# goalLight.net
KiCad netlist of a schematic drawn in Altium Designer
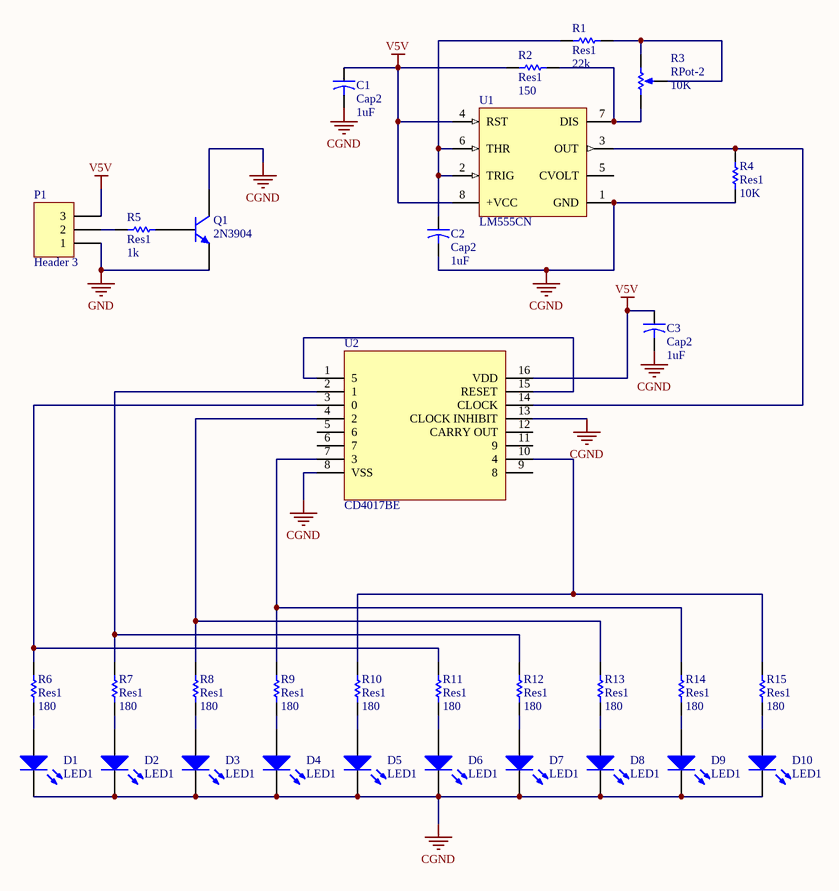
[diagram p0: goalLight.SchDoc]

(export (version "E")
  (design (tool "Eeschema 10.0.6"))
  (components
    (comp (ref "C1")
      (value "Cap2")
      (footprint "CAPR5-4X5")
      (description "Capacitor")
      (fields (field (name "ALTIUM_VALUE") "1uF") (field (name "PUBLISHER") "Altium Limited"))
      (libsource (lib "Miscellaneous Devices") (part "Cap2"))
    )
    (comp (ref "C2")
      (value "Cap2")
      (footprint "CAPR5-4X5")
      (description "Capacitor")
      (fields (field (name "ALTIUM_VALUE") "1uF") (field (name "PUBLISHER") "Altium Limited"))
      (libsource (lib "Miscellaneous Devices") (part "Cap2"))
    )
    (comp (ref "C3")
      (value "Cap2")
      (footprint "CAPR5-4X5")
      (description "Capacitor")
      (fields (field (name "ALTIUM_VALUE") "1uF") (field (name "PUBLISHER") "Altium Limited"))
      (libsource (lib "Miscellaneous Devices") (part "Cap2"))
    )
    (comp (ref "D1")
      (value "LED1")
      (footprint "LED-1")
      (description "Typical RED GaAs LED")
      (fields (field (name "PUBLISHER") "Altium Limited"))
      (libsource (lib "Miscellaneous Devices") (part "LED1"))
    )
    (comp (ref "D2")
      (value "LED1")
      (footprint "LED-1")
      (description "Typical RED GaAs LED")
      (fields (field (name "PUBLISHER") "Altium Limited"))
      (libsource (lib "Miscellaneous Devices") (part "LED1"))
    )
    (comp (ref "D3")
      (value "LED1")
      (footprint "LED-1")
      (description "Typical RED GaAs LED")
      (fields (field (name "PUBLISHER") "Altium Limited"))
      (libsource (lib "Miscellaneous Devices") (part "LED1"))
    )
    (comp (ref "D4")
      (value "LED1")
      (footprint "LED-1")
      (description "Typical RED GaAs LED")
      (fields (field (name "PUBLISHER") "Altium Limited"))
      (libsource (lib "Miscellaneous Devices") (part "LED1"))
    )
    (comp (ref "D5")
      (value "LED1")
      (footprint "LED-1")
      (description "Typical RED GaAs LED")
      (fields (field (name "PUBLISHER") "Altium Limited"))
      (libsource (lib "Miscellaneous Devices") (part "LED1"))
    )
    (comp (ref "D6")
      (value "LED1")
      (footprint "LED-1")
      (description "Typical RED GaAs LED")
      (fields (field (name "PUBLISHER") "Altium Limited"))
      (libsource (lib "Miscellaneous Devices") (part "LED1"))
    )
    (comp (ref "D7")
      (value "LED1")
      (footprint "LED-1")
      (description "Typical RED GaAs LED")
      (fields (field (name "PUBLISHER") "Altium Limited"))
      (libsource (lib "Miscellaneous Devices") (part "LED1"))
    )
    (comp (ref "D8")
      (value "LED1")
      (footprint "LED-1")
      (description "Typical RED GaAs LED")
      (fields (field (name "PUBLISHER") "Altium Limited"))
      (libsource (lib "Miscellaneous Devices") (part "LED1"))
    )
    (comp (ref "D9")
      (value "LED1")
      (footprint "LED-1")
      (description "Typical RED GaAs LED")
      (fields (field (name "PUBLISHER") "Altium Limited"))
      (libsource (lib "Miscellaneous Devices") (part "LED1"))
    )
    (comp (ref "D10")
      (value "LED1")
      (footprint "LED-1")
      (description "Typical RED GaAs LED")
      (fields (field (name "PUBLISHER") "Altium Limited"))
      (libsource (lib "Miscellaneous Devices") (part "LED1"))
    )
    (comp (ref "P1")
      (value "Header 3")
      (footprint "HDR1X3")
      (description "Header, 3-Pin")
      (fields (field (name "PUBLISHER") "Altium Limited"))
      (libsource (lib "Miscellaneous Connectors") (part "Header 3"))
    )
    (comp (ref "Q1")
      (value "2N3904")
      (footprint "TO-92A")
      (description "NPN General Purpose Amplifier")
      (fields (field (name "PUBLISHER") "Altium Limited"))
      (libsource (lib "Miscellaneous Devices") (part "2N3904"))
    )
    (comp (ref "R1")
      (value "Res1")
      (footprint "AXIAL-0.4")
      (description "Resistor")
      (fields (field (name "ALTIUM_VALUE") "22k") (field (name "PUBLISHER") "Altium Limited"))
      (libsource (lib "Miscellaneous Devices") (part "Res1"))
    )
    (comp (ref "R2")
      (value "Res1")
      (footprint "AXIAL-0.4")
      (description "Resistor")
      (fields (field (name "ALTIUM_VALUE") "150") (field (name "PUBLISHER") "Altium Limited"))
      (libsource (lib "Miscellaneous Devices") (part "Res1"))
    )
    (comp (ref "R3")
      (value "RPot-2")
      (footprint "POT3")
      (description "Potentiometer")
      (fields (field (name "ALTIUM_VALUE") "10K") (field (name "PUBLISHER") "Altium Limited"))
      (libsource (lib "components") (part "RPot-2"))
    )
    (comp (ref "R4")
      (value "Res1")
      (footprint "AXIAL-0.4")
      (description "Resistor")
      (fields (field (name "ALTIUM_VALUE") "10K") (field (name "PUBLISHER") "Altium Limited"))
      (libsource (lib "Miscellaneous Devices") (part "Res1"))
    )
    (comp (ref "R5")
      (value "Res1")
      (footprint "AXIAL-0.4")
      (description "Resistor")
      (fields (field (name "ALTIUM_VALUE") "1k") (field (name "PUBLISHER") "Altium Limited"))
      (libsource (lib "Miscellaneous Devices") (part "Res1"))
    )
    (comp (ref "R6")
      (value "Res1")
      (footprint "AXIAL-0.4")
      (description "Resistor")
      (fields (field (name "ALTIUM_VALUE") "180") (field (name "PUBLISHER") "Altium Limited"))
      (libsource (lib "Miscellaneous Devices") (part "Res1"))
    )
    (comp (ref "R7")
      (value "Res1")
      (footprint "AXIAL-0.4")
      (description "Resistor")
      (fields (field (name "ALTIUM_VALUE") "180") (field (name "PUBLISHER") "Altium Limited"))
      (libsource (lib "Miscellaneous Devices") (part "Res1"))
    )
    (comp (ref "R8")
      (value "Res1")
      (footprint "AXIAL-0.4")
      (description "Resistor")
      (fields (field (name "ALTIUM_VALUE") "180") (field (name "PUBLISHER") "Altium Limited"))
      (libsource (lib "Miscellaneous Devices") (part "Res1"))
    )
    (comp (ref "R9")
      (value "Res1")
      (footprint "AXIAL-0.4")
      (description "Resistor")
      (fields (field (name "ALTIUM_VALUE") "180") (field (name "PUBLISHER") "Altium Limited"))
      (libsource (lib "Miscellaneous Devices") (part "Res1"))
    )
    (comp (ref "R10")
      (value "Res1")
      (footprint "AXIAL-0.4")
      (description "Resistor")
      (fields (field (name "ALTIUM_VALUE") "180") (field (name "PUBLISHER") "Altium Limited"))
      (libsource (lib "Miscellaneous Devices") (part "Res1"))
    )
    (comp (ref "R11")
      (value "Res1")
      (footprint "AXIAL-0.4")
      (description "Resistor")
      (fields (field (name "ALTIUM_VALUE") "180") (field (name "PUBLISHER") "Altium Limited"))
      (libsource (lib "Miscellaneous Devices") (part "Res1"))
    )
    (comp (ref "R12")
      (value "Res1")
      (footprint "AXIAL-0.4")
      (description "Resistor")
      (fields (field (name "ALTIUM_VALUE") "180") (field (name "PUBLISHER") "Altium Limited"))
      (libsource (lib "Miscellaneous Devices") (part "Res1"))
    )
    (comp (ref "R13")
      (value "Res1")
      (footprint "AXIAL-0.4")
      (description "Resistor")
      (fields (field (name "ALTIUM_VALUE") "180") (field (name "PUBLISHER") "Altium Limited"))
      (libsource (lib "Miscellaneous Devices") (part "Res1"))
    )
    (comp (ref "R14")
      (value "Res1")
      (footprint "AXIAL-0.4")
      (description "Resistor")
      (fields (field (name "ALTIUM_VALUE") "180") (field (name "PUBLISHER") "Altium Limited"))
      (libsource (lib "Miscellaneous Devices") (part "Res1"))
    )
    (comp (ref "R15")
      (value "Res1")
      (footprint "AXIAL-0.4")
      (description "Resistor")
      (fields (field (name "ALTIUM_VALUE") "180") (field (name "PUBLISHER") "Altium Limited"))
      (libsource (lib "Miscellaneous Devices") (part "Res1"))
    )
    (comp (ref "U1")
      (value "LM555CN")
      (footprint "N08E")
      (description "Timer, 8-pin MDIP")
      (fields
        (field (name "MANUFACTURER") "National Semiconductor")
        (field (name "PUBLISHER") "Altium Limited")
      )
      (libsource (lib "NSC Analog") (part "LM555CN"))
    )
    (comp (ref "U2")
      (value "CD4017BE")
      (footprint "N16")
      (description "Decade Counter")
      (libsource (lib "components") (part "CD4017BE"))
    )
  )
  (nets
    (net (code "1") (name "CGND") (class "Default")
      (node (ref "C1") (pin "2") (pinfunction "2_2") (pintype "passive"))
      (node (ref "C2") (pin "2") (pinfunction "2_2") (pintype "passive"))
      (node (ref "C3") (pin "2") (pinfunction "2_2") (pintype "passive"))
      (node (ref "D1") (pin "2") (pinfunction "K_2") (pintype "passive"))
      (node (ref "D10") (pin "2") (pinfunction "K_2") (pintype "passive"))
      (node (ref "D2") (pin "2") (pinfunction "K_2") (pintype "passive"))
      (node (ref "D3") (pin "2") (pinfunction "K_2") (pintype "passive"))
      (node (ref "D4") (pin "2") (pinfunction "K_2") (pintype "passive"))
      (node (ref "D5") (pin "2") (pinfunction "K_2") (pintype "passive"))
      (node (ref "D6") (pin "2") (pinfunction "K_2") (pintype "passive"))
      (node (ref "D7") (pin "2") (pinfunction "K_2") (pintype "passive"))
      (node (ref "D8") (pin "2") (pinfunction "K_2") (pintype "passive"))
      (node (ref "D9") (pin "2") (pinfunction "K_2") (pintype "passive"))
      (node (ref "Q1") (pin "3") (pinfunction "C_3") (pintype "passive"))
      (node (ref "R4") (pin "1") (pinfunction "1_1") (pintype "passive"))
      (node (ref "U1") (pin "1") (pinfunction "GND_1") (pintype "power_in"))
      (node (ref "U2") (pin "13") (pinfunction "CLOCK_INHIBIT_13") (pintype "passive"))
      (node (ref "U2") (pin "8") (pinfunction "VSS_8") (pintype "passive"))
    )
    (net (code "2") (name "GND") (class "Default")
      (node (ref "P1") (pin "1") (pinfunction "1_1") (pintype "passive"))
      (node (ref "Q1") (pin "1") (pinfunction "E_1") (pintype "passive"))
    )
    (net (code "3") (name "Net-(D1-A)") (class "Default")
      (node (ref "D1") (pin "1") (pinfunction "A_1") (pintype "passive"))
      (node (ref "R6") (pin "1") (pinfunction "1_1") (pintype "passive"))
    )
    (net (code "4") (name "Net-(D2-A)") (class "Default")
      (node (ref "D2") (pin "1") (pinfunction "A_1") (pintype "passive"))
      (node (ref "R7") (pin "1") (pinfunction "1_1") (pintype "passive"))
    )
    (net (code "5") (name "Net-(D3-A)") (class "Default")
      (node (ref "D3") (pin "1") (pinfunction "A_1") (pintype "passive"))
      (node (ref "R8") (pin "1") (pinfunction "1_1") (pintype "passive"))
    )
    (net (code "6") (name "Net-(D4-A)") (class "Default")
      (node (ref "D4") (pin "1") (pinfunction "A_1") (pintype "passive"))
      (node (ref "R9") (pin "1") (pinfunction "1_1") (pintype "passive"))
    )
    (net (code "7") (name "Net-(D5-A)") (class "Default")
      (node (ref "D5") (pin "1") (pinfunction "A_1") (pintype "passive"))
      (node (ref "R10") (pin "1") (pinfunction "1_1") (pintype "passive"))
    )
    (net (code "8") (name "Net-(D6-A)") (class "Default")
      (node (ref "D6") (pin "1") (pinfunction "A_1") (pintype "passive"))
      (node (ref "R11") (pin "1") (pinfunction "1_1") (pintype "passive"))
    )
    (net (code "9") (name "Net-(D7-A)") (class "Default")
      (node (ref "D7") (pin "1") (pinfunction "A_1") (pintype "passive"))
      (node (ref "R12") (pin "1") (pinfunction "1_1") (pintype "passive"))
    )
    (net (code "10") (name "Net-(D8-A)") (class "Default")
      (node (ref "D8") (pin "1") (pinfunction "A_1") (pintype "passive"))
      (node (ref "R13") (pin "1") (pinfunction "1_1") (pintype "passive"))
    )
    (net (code "11") (name "Net-(D9-A)") (class "Default")
      (node (ref "D9") (pin "1") (pinfunction "A_1") (pintype "passive"))
      (node (ref "R14") (pin "1") (pinfunction "1_1") (pintype "passive"))
    )
    (net (code "12") (name "Net-(D10-A)") (class "Default")
      (node (ref "D10") (pin "1") (pinfunction "A_1") (pintype "passive"))
      (node (ref "R15") (pin "1") (pinfunction "1_1") (pintype "passive"))
    )
    (net (code "13") (name "Net-(P1-Pad2)") (class "Default")
      (node (ref "P1") (pin "2") (pinfunction "2_2") (pintype "passive"))
      (node (ref "R5") (pin "2") (pinfunction "2_2") (pintype "passive"))
    )
    (net (code "14") (name "Net-(Q1-B)") (class "Default")
      (node (ref "Q1") (pin "2") (pinfunction "B_2") (pintype "passive"))
      (node (ref "R5") (pin "1") (pinfunction "1_1") (pintype "passive"))
    )
    (net (code "15") (name "Net-(R3-BOT)") (class "Default")
      (node (ref "R1") (pin "1") (pinfunction "1_1") (pintype "passive"))
      (node (ref "R3") (pin "2") (pinfunction "BOT_2") (pintype "passive"))
      (node (ref "R3") (pin "3") (pinfunction "TAP_3") (pintype "passive"))
    )
    (net (code "16") (name "Net-(R3-TOP)") (class "Default")
      (node (ref "R2") (pin "1") (pinfunction "1_1") (pintype "passive"))
      (node (ref "R3") (pin "1") (pinfunction "TOP_1") (pintype "passive"))
      (node (ref "U1") (pin "7") (pinfunction "DIS_7") (pintype "open_collector"))
    )
    (net (code "17") (name "Net-(U1-OUT)") (class "Default")
      (node (ref "R4") (pin "2") (pinfunction "2_2") (pintype "passive"))
      (node (ref "U1") (pin "3") (pinfunction "OUT_3") (pintype "output"))
      (node (ref "U2") (pin "14") (pinfunction "CLOCK_14") (pintype "passive"))
    )
    (net (code "18") (name "Net-(U1-THR)") (class "Default")
      (node (ref "C2") (pin "1") (pinfunction "1_1") (pintype "passive"))
      (node (ref "R1") (pin "2") (pinfunction "2_2") (pintype "passive"))
      (node (ref "U1") (pin "2") (pinfunction "TRIG_2") (pintype "input"))
      (node (ref "U1") (pin "6") (pinfunction "THR_6") (pintype "input"))
    )
    (net (code "19") (name "Net-(U2-0)") (class "Default")
      (node (ref "R11") (pin "2") (pinfunction "2_2") (pintype "passive"))
      (node (ref "R6") (pin "2") (pinfunction "2_2") (pintype "passive"))
      (node (ref "U2") (pin "3") (pinfunction "0_3") (pintype "passive"))
    )
    (net (code "20") (name "Net-(U2-1)") (class "Default")
      (node (ref "R12") (pin "2") (pinfunction "2_2") (pintype "passive"))
      (node (ref "R7") (pin "2") (pinfunction "2_2") (pintype "passive"))
      (node (ref "U2") (pin "2") (pinfunction "1_2") (pintype "passive"))
    )
    (net (code "21") (name "Net-(U2-2)") (class "Default")
      (node (ref "R13") (pin "2") (pinfunction "2_2") (pintype "passive"))
      (node (ref "R8") (pin "2") (pinfunction "2_2") (pintype "passive"))
      (node (ref "U2") (pin "4") (pinfunction "2_4") (pintype "passive"))
    )
    (net (code "22") (name "Net-(U2-3)") (class "Default")
      (node (ref "R14") (pin "2") (pinfunction "2_2") (pintype "passive"))
      (node (ref "R9") (pin "2") (pinfunction "2_2") (pintype "passive"))
      (node (ref "U2") (pin "7") (pinfunction "3_7") (pintype "passive"))
    )
    (net (code "23") (name "Net-(U2-4)") (class "Default")
      (node (ref "R10") (pin "2") (pinfunction "2_2") (pintype "passive"))
      (node (ref "R15") (pin "2") (pinfunction "2_2") (pintype "passive"))
      (node (ref "U2") (pin "10") (pinfunction "4_10") (pintype "passive"))
    )
    (net (code "24") (name "Net-(U2-5)") (class "Default")
      (node (ref "U2") (pin "1") (pinfunction "5_1") (pintype "passive"))
      (node (ref "U2") (pin "15") (pinfunction "RESET_15") (pintype "passive"))
    )
    (net (code "25") (name "V5V") (class "Default")
      (node (ref "C1") (pin "1") (pinfunction "1_1") (pintype "passive"))
      (node (ref "C3") (pin "1") (pinfunction "1_1") (pintype "passive"))
      (node (ref "P1") (pin "3") (pinfunction "3_3") (pintype "passive"))
      (node (ref "R2") (pin "2") (pinfunction "2_2") (pintype "passive"))
      (node (ref "U1") (pin "4") (pinfunction "RST_4") (pintype "input"))
      (node (ref "U1") (pin "8") (pinfunction "+VCC_8") (pintype "power_in"))
      (node (ref "U2") (pin "16") (pinfunction "VDD_16") (pintype "passive"))
    )
    (net (code "26") (name "unconnected-(U1-CVOLT-Pad5)") (class "Default")
      (node (ref "U1") (pin "5") (pinfunction "CVOLT_5") (pintype "passive"))
    )
    (net (code "27") (name "unconnected-(U2-6-Pad5)") (class "Default")
      (node (ref "U2") (pin "5") (pinfunction "6_5") (pintype "passive"))
    )
    (net (code "28") (name "unconnected-(U2-7-Pad6)") (class "Default")
      (node (ref "U2") (pin "6") (pinfunction "7_6") (pintype "passive"))
    )
    (net (code "29") (name "unconnected-(U2-8-Pad9)") (class "Default")
      (node (ref "U2") (pin "9") (pinfunction "8_9") (pintype "passive"))
    )
    (net (code "30") (name "unconnected-(U2-9-Pad11)") (class "Default")
      (node (ref "U2") (pin "11") (pinfunction "9_11") (pintype "passive"))
    )
    (net (code "31") (name "unconnected-(U2-CARRY_OUT-Pad12)") (class "Default")
      (node (ref "U2") (pin "12") (pinfunction "CARRY_OUT_12") (pintype "passive"))
    )
  )
)
